# BalancingNetwork.net
KiCad netlist of a schematic drawn in Altium Designer
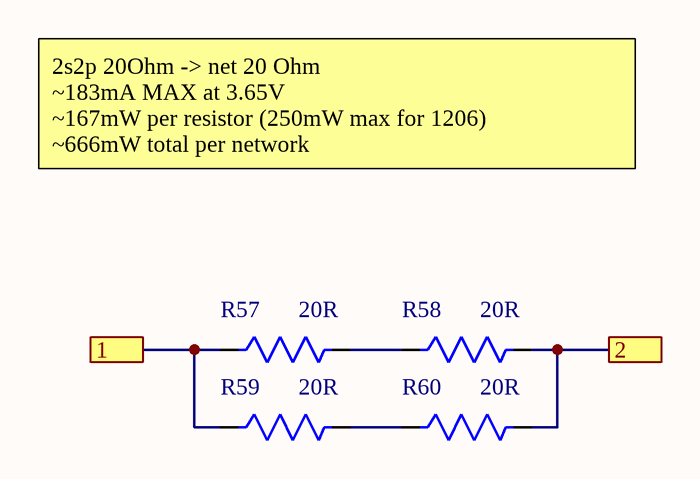
[diagram p0: BalancingNetwork.SchDoc]

(export (version "E")
  (design (tool "Eeschema 10.0.6"))
  (components
    (comp (ref "R57")
      (value "20R")
      (footprint "RES_SM1206_YAGEORC_N")
      (description "GTT Standard 1206 Resistor")
      (fields (field (name "TOLERANCE") "1%") (field (name "POWER") "250mW"))
      (libsource (lib "Green Team Twente") (part "RES_GENERIC"))
    )
    (comp (ref "R58")
      (value "20R")
      (footprint "RES_SM1206_YAGEORC_N")
      (description "GTT Standard 1206 Resistor")
      (fields (field (name "TOLERANCE") "1%") (field (name "POWER") "250mW"))
      (libsource (lib "Green Team Twente") (part "RES_GENERIC"))
    )
    (comp (ref "R59")
      (value "20R")
      (footprint "RES_SM1206_YAGEORC_N")
      (description "GTT Standard 1206 Resistor")
      (fields (field (name "TOLERANCE") "1%") (field (name "POWER") "250mW"))
      (libsource (lib "Green Team Twente") (part "RES_GENERIC"))
    )
    (comp (ref "R60")
      (value "20R")
      (footprint "RES_SM1206_YAGEORC_N")
      (description "GTT Standard 1206 Resistor")
      (fields (field (name "TOLERANCE") "1%") (field (name "POWER") "250mW"))
      (libsource (lib "Green Team Twente") (part "RES_GENERIC"))
    )
  )
  (nets
    (net (code "1") (name "/1") (class "Default")
      (node (ref "R57") (pin "1") (pinfunction "1_1") (pintype "passive"))
      (node (ref "R59") (pin "1") (pinfunction "1_1") (pintype "passive"))
    )
    (net (code "2") (name "/2") (class "Default")
      (node (ref "R58") (pin "2") (pinfunction "2_2") (pintype "passive"))
      (node (ref "R60") (pin "2") (pinfunction "2_2") (pintype "passive"))
    )
    (net (code "3") (name "Net-(R57-Pad2)") (class "Default")
      (node (ref "R57") (pin "2") (pinfunction "2_2") (pintype "passive"))
      (node (ref "R58") (pin "1") (pinfunction "1_1") (pintype "passive"))
    )
    (net (code "4") (name "Net-(R59-Pad2)") (class "Default")
      (node (ref "R59") (pin "2") (pinfunction "2_2") (pintype "passive"))
      (node (ref "R60") (pin "1") (pinfunction "1_1") (pintype "passive"))
    )
  )
)
